# door_FM_rev_B.net
KiCad netlist of a schematic drawn in EAGLE
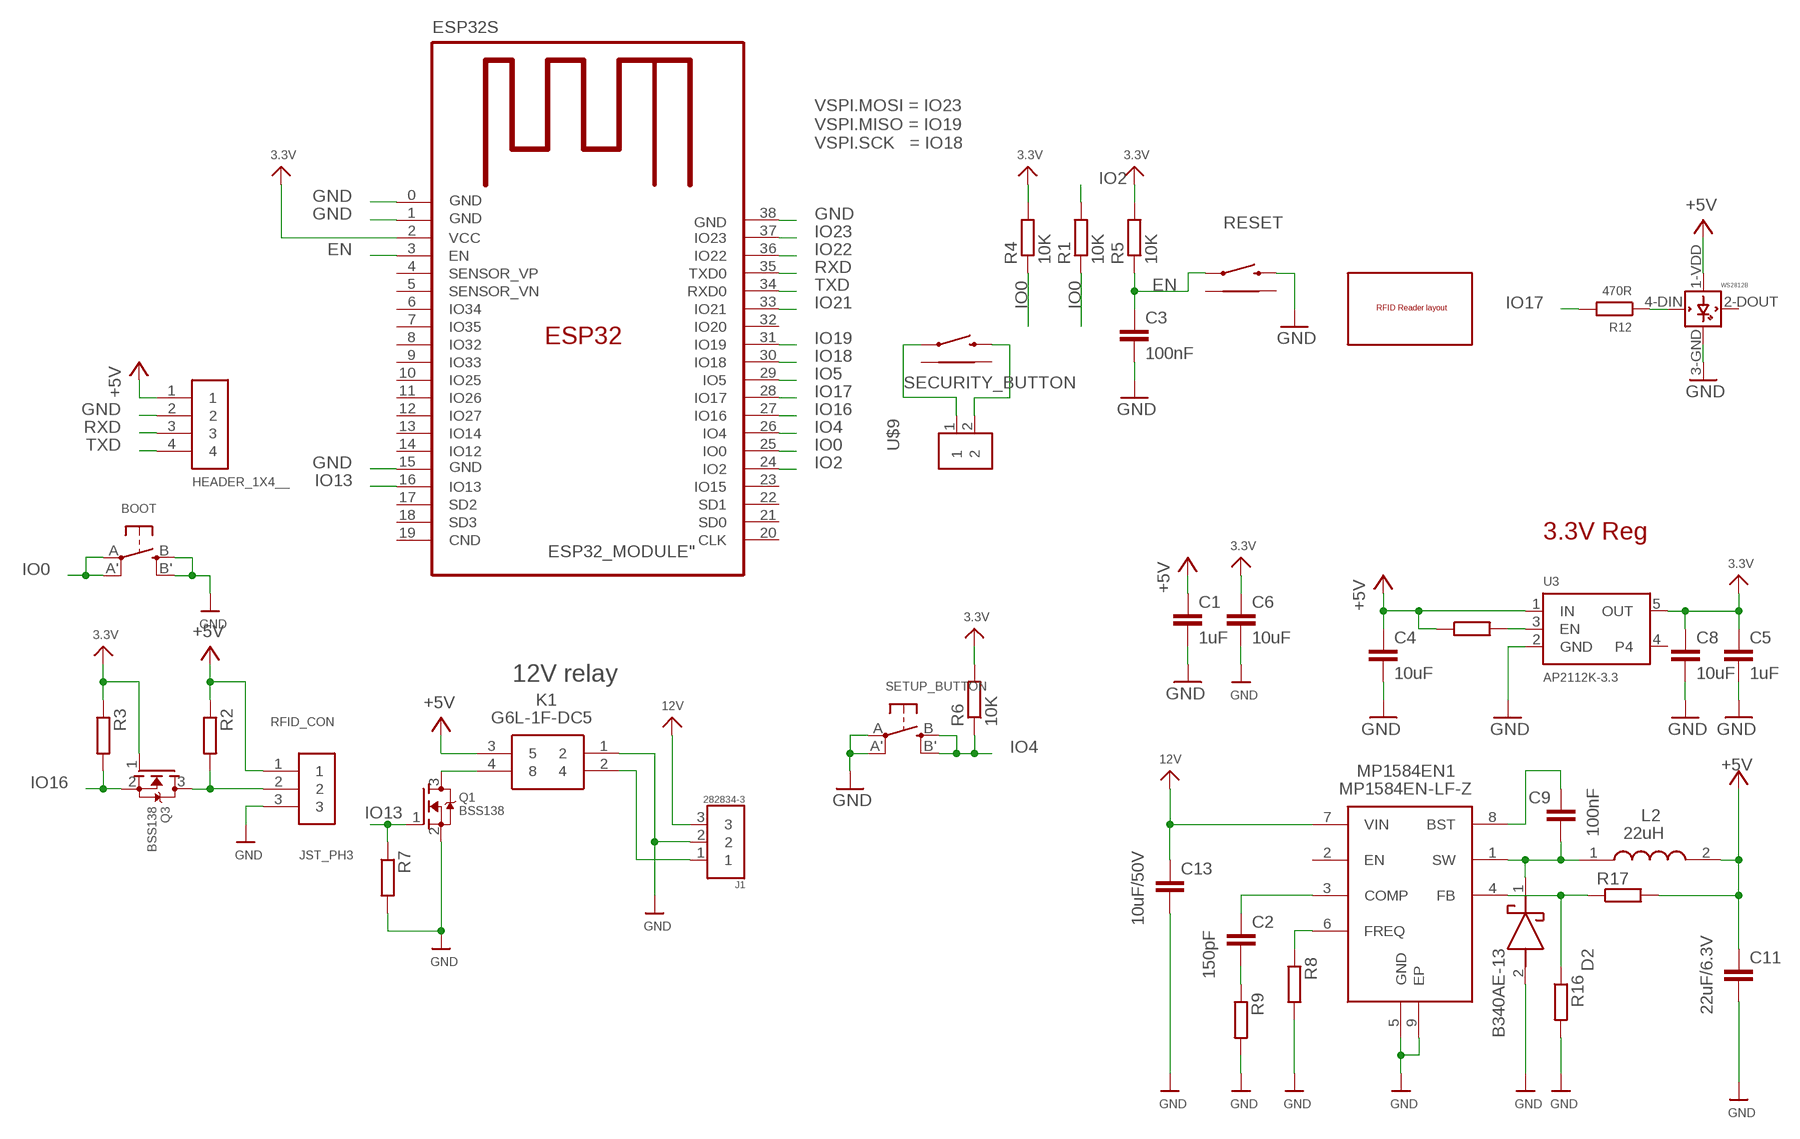
[diagram p0: schematic, sheet 1]

(export (version "E")
  (design (tool "Eeschema 10.0.6"))
  (components
    (comp (ref "BOOT")
      (value "BUTTON_KMR2_4.6X2.8")
      (footprint "eagle-import:BUTTON_KMR2_4.6X2.8")
      (libsource (lib "eagle-import") (part "BUTTON_KMR2_4.6X2.8"))
    )
    (comp (ref "C1")
      (value "1uF")
      (footprint "eagle-import:C0805")
      (libsource (lib "eagle-import") (part "C-EUC0805"))
    )
    (comp (ref "C2")
      (value "150pF")
      (footprint "eagle-import:C0805")
      (libsource (lib "eagle-import") (part "C-EUC0805"))
    )
    (comp (ref "C3")
      (value "100nF")
      (footprint "eagle-import:C0805")
      (libsource (lib "eagle-import") (part "C-EUC0805"))
    )
    (comp (ref "C4")
      (value "10uF")
      (footprint "eagle-import:C0805")
      (libsource (lib "eagle-import") (part "C-EUC0805"))
    )
    (comp (ref "C5")
      (value "1uF")
      (footprint "eagle-import:C0805")
      (libsource (lib "eagle-import") (part "C-EUC0805"))
    )
    (comp (ref "C6")
      (value "10uF")
      (footprint "eagle-import:C0805")
      (libsource (lib "eagle-import") (part "C-EUC0805"))
    )
    (comp (ref "C8")
      (value "10uF")
      (footprint "eagle-import:C0805")
      (libsource (lib "eagle-import") (part "C-EUC0805"))
    )
    (comp (ref "C9")
      (value "100nF")
      (footprint "eagle-import:C0805")
      (libsource (lib "eagle-import") (part "C-EUC0805"))
    )
    (comp (ref "C11")
      (value "22uF/6.3V")
      (footprint "eagle-import:C0805")
      (libsource (lib "eagle-import") (part "C-EUC0805"))
    )
    (comp (ref "C13")
      (value "10uF/50V")
      (footprint "eagle-import:C1206")
      (libsource (lib "eagle-import") (part "C-EUC1206"))
    )
    (comp (ref "CN1")
      (value "HEADER_1X4__")
      (footprint "eagle-import:HEADER_1X4_RIGHT_ANGLE")
      (libsource (lib "eagle-import") (part "HEADER_1X4__"))
    )
    (comp (ref "D2")
      (value "B340AE-13")
      (footprint "eagle-import:DIOM5226X240N")
      (fields (field (name "MOUSER_PART_NUMBER") "621-B340AE-13"))
      (libsource (lib "eagle-import") (part "B340AE-13"))
    )
    (comp (ref "ESP32S")
      (value "ESP32_MODULE\"")
      (footprint "eagle-import:ESP32_MODULE")
      (libsource (lib "eagle-import") (part "ESP32_MODULE{dblquote}"))
    )
    (comp (ref "J1")
      (value "282834-3")
      (footprint "eagle-import:TE_282834-3")
      (fields (field (name "MF") "TE Connectivity"))
      (libsource (lib "eagle-import") (part "282834-3"))
    )
    (comp (ref "K1")
      (value "G6L-1F-DC5")
      (footprint "eagle-import:G6L-1F-DC5")
      (fields (field (name "MOUSER_PART_NUMBER") "653-G6L-1F-DC5"))
      (libsource (lib "eagle-import") (part "G6L-1F-DC5"))
    )
    (comp (ref "L2")
      (value "22uH")
      (footprint "eagle-import:ASPI-0630LR")
      (fields
        (field (name "MANUFACTURER_PART_NUMBER") "ASPI-0630LR-4R7M-T15")
        (field (name "MOUSER_PART_NUMBER") "815-ASPI0630LR4R7T15")
      )
      (libsource (lib "eagle-import") (part "ASPI-0630LR-4R7M-T15"))
    )
    (comp (ref "MP1584EN1")
      (value "MP1584EN-LF-Z")
      (footprint "eagle-import:SOIC127P600X170-9N")
      (fields (field (name "MOUSER_PART_NUMBER") "946-MP1584ENLFZ"))
      (libsource (lib "eagle-import") (part "MP1584EN-LF-Z"))
    )
    (comp (ref "Q1")
      (value "BSS138")
      (footprint "eagle-import:SOT95P240X110-3")
      (libsource (lib "eagle-import") (part "MOSFET_N_"))
    )
    (comp (ref "Q3")
      (value "BSS138")
      (footprint "eagle-import:SOT95P240X110-3")
      (libsource (lib "eagle-import") (part "MOSFET_N_"))
    )
    (comp (ref "R1")
      (value "10K")
      (footprint "eagle-import:R0805")
      (libsource (lib "eagle-import") (part "R-EU_R0805"))
    )
    (comp (ref "R2")
      (value "10K")
      (footprint "eagle-import:R0805")
      (libsource (lib "eagle-import") (part "R-EU_R0805"))
    )
    (comp (ref "R3")
      (value "10K")
      (footprint "eagle-import:R0805")
      (libsource (lib "eagle-import") (part "R-EU_R0805"))
    )
    (comp (ref "R4")
      (value "10K")
      (footprint "eagle-import:R0805")
      (libsource (lib "eagle-import") (part "R-EU_R0805"))
    )
    (comp (ref "R5")
      (value "10K")
      (footprint "eagle-import:R0805")
      (libsource (lib "eagle-import") (part "R-EU_R0805"))
    )
    (comp (ref "R6")
      (value "10K")
      (footprint "eagle-import:R0805")
      (libsource (lib "eagle-import") (part "R-EU_R0805"))
    )
    (comp (ref "R7")
      (value "10K")
      (footprint "eagle-import:R0805")
      (libsource (lib "eagle-import") (part "R-EU_R0805"))
    )
    (comp (ref "R8")
      (value "100K")
      (footprint "eagle-import:R0805")
      (libsource (lib "eagle-import") (part "R-EU_R0805"))
    )
    (comp (ref "R9")
      (value "100K")
      (footprint "eagle-import:R0805")
      (libsource (lib "eagle-import") (part "R-EU_R0805"))
    )
    (comp (ref "R12")
      (value "470R")
      (footprint "eagle-import:R0805")
      (libsource (lib "eagle-import") (part "R-EU_R0805"))
    )
    (comp (ref "R16")
      (value "40K2")
      (footprint "eagle-import:R0805")
      (libsource (lib "eagle-import") (part "R-EU_R0805"))
    )
    (comp (ref "R17")
      (value "210K")
      (footprint "eagle-import:R0805")
      (libsource (lib "eagle-import") (part "R-EU_R0805"))
    )
    (comp (ref "R19")
      (value "10K")
      (footprint "eagle-import:R0805")
      (libsource (lib "eagle-import") (part "R-EU_R0805"))
    )
    (comp (ref "RESET")
      (value "TACTILE_SWITCH_RIGHT_ANGLE_THT_")
      (footprint "eagle-import:TACTILE_SWITCH_RIGHT_ANGLE_THT")
      (libsource (lib "eagle-import") (part "TACTILE_SWITCH_RIGHT_ANGLE_THT_"))
    )
    (comp (ref "RFID_CON")
      (value "JST_PH3")
      (footprint "eagle-import:JST-PH3")
      (libsource (lib "eagle-import") (part "JST_PH3"))
    )
    (comp (ref "SECURITY_BUTTON")
      (value "TACTILE_SWITCH_RIGHT_ANGLE_THT_")
      (footprint "eagle-import:TACTILE_SWITCH_RIGHT_ANGLE_THT")
      (libsource (lib "eagle-import") (part "TACTILE_SWITCH_RIGHT_ANGLE_THT_"))
    )
    (comp (ref "SETUP_BUTTON")
      (value "BUTTON_KMR2_4.6X2.8")
      (footprint "eagle-import:BUTTON_KMR2_4.6X2.8")
      (libsource (lib "eagle-import") (part "BUTTON_KMR2_4.6X2.8"))
    )
    (comp (ref "U$9")
      (value "282834-2")
      (footprint "eagle-import:CONN_282834-2")
      (fields (field (name "MF") "TE Connectivity"))
      (libsource (lib "eagle-import") (part "282834-2"))
    )
    (comp (ref "U$10")
      (value "RFID_READER")
      (footprint "eagle-import:RFID_READER")
      (libsource (lib "eagle-import") (part "RFID_READER"))
    )
    (comp (ref "U3")
      (value "AP2112K-3.3")
      (footprint "eagle-import:SOT95P290X120-5")
      (libsource (lib "eagle-import") (part "AP2112K-3.3_"))
    )
    (comp (ref "WS2812B")
      (value "WS2812B__")
      (footprint "eagle-import:WS2812B_5050")
      (libsource (lib "eagle-import") (part "WS2812B__"))
    )
  )
  (nets
    (net (code "1") (name "+5V") (class "Default")
      (node (ref "C1") (pin "1") (pinfunction "1_1") (pintype "passive"))
      (node (ref "C11") (pin "1") (pinfunction "1_1") (pintype "passive"))
      (node (ref "C4") (pin "1") (pinfunction "1_1") (pintype "passive"))
      (node (ref "CN1") (pin "1") (pinfunction "1_1") (pintype "bidirectional"))
      (node (ref "K1") (pin "3") (pinfunction "5_3") (pintype "bidirectional"))
      (node (ref "L2") (pin "2") (pinfunction "2_2") (pintype "bidirectional"))
      (node (ref "R17") (pin "2") (pinfunction "2_2") (pintype "passive"))
      (node (ref "R19") (pin "1") (pinfunction "1_1") (pintype "passive"))
      (node (ref "R2") (pin "1") (pinfunction "1_1") (pintype "passive"))
      (node (ref "RFID_CON") (pin "1") (pinfunction "1_1") (pintype "bidirectional"))
      (node (ref "U3") (pin "1") (pinfunction "IN_1") (pintype "bidirectional"))
      (node (ref "WS2812B") (pin "1-VDD") (pinfunction "VDD_1-VDD") (pintype "bidirectional"))
    )
    (net (code "2") (name "/EN") (class "Default")
      (node (ref "C3") (pin "1") (pinfunction "1_1") (pintype "passive"))
      (node (ref "ESP32S") (pin "3") (pinfunction "EN_3") (pintype "bidirectional"))
      (node (ref "R5") (pin "1") (pinfunction "1_1") (pintype "passive"))
      (node (ref "RESET") (pin "1") (pinfunction "1_1") (pintype "passive"))
    )
    (net (code "3") (name "/IO0") (class "Default")
      (node (ref "BOOT") (pin "A") (pinfunction "P_A") (pintype "passive"))
      (node (ref "BOOT") (pin "A'") (pinfunction "P1_A'") (pintype "passive"))
      (node (ref "ESP32S") (pin "25") (pinfunction "IO0_25") (pintype "bidirectional"))
      (node (ref "R1") (pin "1") (pinfunction "1_1") (pintype "passive"))
      (node (ref "R4") (pin "1") (pinfunction "1_1") (pintype "passive"))
    )
    (net (code "4") (name "/IO2") (class "Default")
      (node (ref "ESP32S") (pin "24") (pinfunction "IO2_24") (pintype "bidirectional"))
      (node (ref "R1") (pin "2") (pinfunction "2_2") (pintype "passive"))
    )
    (net (code "5") (name "/IO4") (class "Default")
      (node (ref "ESP32S") (pin "26") (pinfunction "IO4_26") (pintype "bidirectional"))
      (node (ref "R6") (pin "1") (pinfunction "1_1") (pintype "passive"))
      (node (ref "SETUP_BUTTON") (pin "B") (pinfunction "S_B") (pintype "passive"))
      (node (ref "SETUP_BUTTON") (pin "B'") (pinfunction "S1_B'") (pintype "passive"))
    )
    (net (code "6") (name "/IO5") (class "Default")
      (node (ref "ESP32S") (pin "29") (pinfunction "IO5_29") (pintype "bidirectional"))
    )
    (net (code "7") (name "/IO13") (class "Default")
      (node (ref "ESP32S") (pin "16") (pinfunction "IO13_16") (pintype "bidirectional"))
      (node (ref "Q1") (pin "1") (pinfunction "G_1") (pintype "bidirectional"))
      (node (ref "R7") (pin "1") (pinfunction "1_1") (pintype "passive"))
    )
    (net (code "8") (name "/IO16") (class "Default")
      (node (ref "ESP32S") (pin "27") (pinfunction "IO16_27") (pintype "bidirectional"))
      (node (ref "Q3") (pin "2") (pinfunction "S_2") (pintype "bidirectional"))
      (node (ref "R3") (pin "2") (pinfunction "2_2") (pintype "passive"))
    )
    (net (code "9") (name "/IO17") (class "Default")
      (node (ref "ESP32S") (pin "28") (pinfunction "IO17_28") (pintype "bidirectional"))
      (node (ref "R12") (pin "2") (pinfunction "2_2") (pintype "passive"))
    )
    (net (code "10") (name "/IO18") (class "Default")
      (node (ref "ESP32S") (pin "30") (pinfunction "IO18_30") (pintype "bidirectional"))
    )
    (net (code "11") (name "/IO19") (class "Default")
      (node (ref "ESP32S") (pin "31") (pinfunction "IO19_31") (pintype "bidirectional"))
    )
    (net (code "12") (name "/IO21") (class "Default")
      (node (ref "ESP32S") (pin "33") (pinfunction "IO21_33") (pintype "bidirectional"))
    )
    (net (code "13") (name "/IO22") (class "Default")
      (node (ref "ESP32S") (pin "36") (pinfunction "IO22_36") (pintype "bidirectional"))
    )
    (net (code "14") (name "/IO23") (class "Default")
      (node (ref "ESP32S") (pin "37") (pinfunction "IO23_37") (pintype "bidirectional"))
    )
    (net (code "15") (name "/RXD") (class "Default")
      (node (ref "CN1") (pin "3") (pinfunction "3_3") (pintype "bidirectional"))
      (node (ref "ESP32S") (pin "35") (pinfunction "TXD0_35") (pintype "bidirectional"))
    )
    (net (code "16") (name "/TXD") (class "Default")
      (node (ref "CN1") (pin "4") (pinfunction "4_4") (pintype "bidirectional"))
      (node (ref "ESP32S") (pin "34") (pinfunction "RXD0_34") (pintype "bidirectional"))
    )
    (net (code "17") (name "3.3V") (class "Default")
      (node (ref "C5") (pin "1") (pinfunction "1_1") (pintype "passive"))
      (node (ref "C6") (pin "1") (pinfunction "1_1") (pintype "passive"))
      (node (ref "C8") (pin "1") (pinfunction "1_1") (pintype "passive"))
      (node (ref "ESP32S") (pin "2") (pinfunction "VCC_2") (pintype "power_in"))
      (node (ref "Q3") (pin "1") (pinfunction "G_1") (pintype "bidirectional"))
      (node (ref "R3") (pin "1") (pinfunction "1_1") (pintype "passive"))
      (node (ref "R4") (pin "2") (pinfunction "2_2") (pintype "passive"))
      (node (ref "R5") (pin "2") (pinfunction "2_2") (pintype "passive"))
      (node (ref "R6") (pin "2") (pinfunction "2_2") (pintype "passive"))
      (node (ref "U3") (pin "5") (pinfunction "OUT_5") (pintype "bidirectional"))
    )
    (net (code "18") (name "12V") (class "Default")
      (node (ref "C13") (pin "1") (pinfunction "1_1") (pintype "passive"))
      (node (ref "J1") (pin "3") (pinfunction "3_3") (pintype "passive"))
      (node (ref "MP1584EN1") (pin "7") (pinfunction "VIN_7") (pintype "power_in"))
    )
    (net (code "19") (name "GND") (class "Default")
      (node (ref "BOOT") (pin "B") (pinfunction "S_B") (pintype "passive"))
      (node (ref "BOOT") (pin "B'") (pinfunction "S1_B'") (pintype "passive"))
      (node (ref "C1") (pin "2") (pinfunction "2_2") (pintype "passive"))
      (node (ref "C11") (pin "2") (pinfunction "2_2") (pintype "passive"))
      (node (ref "C13") (pin "2") (pinfunction "2_2") (pintype "passive"))
      (node (ref "C3") (pin "2") (pinfunction "2_2") (pintype "passive"))
      (node (ref "C4") (pin "2") (pinfunction "2_2") (pintype "passive"))
      (node (ref "C5") (pin "2") (pinfunction "2_2") (pintype "passive"))
      (node (ref "C6") (pin "2") (pinfunction "2_2") (pintype "passive"))
      (node (ref "C8") (pin "2") (pinfunction "2_2") (pintype "passive"))
      (node (ref "CN1") (pin "2") (pinfunction "2_2") (pintype "bidirectional"))
      (node (ref "D2") (pin "2") (pinfunction "A_2") (pintype "bidirectional"))
      (node (ref "ESP32S") (pin "0") (pinfunction "GND_0") (pintype "power_in"))
      (node (ref "ESP32S") (pin "1") (pinfunction "GND_1") (pintype "power_in"))
      (node (ref "ESP32S") (pin "15") (pinfunction "GND_15") (pintype "power_in"))
      (node (ref "ESP32S") (pin "38") (pinfunction "GND_38") (pintype "power_in"))
      (node (ref "J1") (pin "2") (pinfunction "2_2") (pintype "passive"))
      (node (ref "K1") (pin "1") (pinfunction "2_1") (pintype "bidirectional"))
      (node (ref "MP1584EN1") (pin "5") (pinfunction "GND_5") (pintype "power_in"))
      (node (ref "MP1584EN1") (pin "9") (pinfunction "EP_9") (pintype "bidirectional"))
      (node (ref "Q1") (pin "2") (pinfunction "S_2") (pintype "bidirectional"))
      (node (ref "R16") (pin "2") (pinfunction "2_2") (pintype "passive"))
      (node (ref "R7") (pin "2") (pinfunction "2_2") (pintype "passive"))
      (node (ref "R8") (pin "2") (pinfunction "2_2") (pintype "passive"))
      (node (ref "R9") (pin "2") (pinfunction "2_2") (pintype "passive"))
      (node (ref "RESET") (pin "2") (pinfunction "2_2") (pintype "passive"))
      (node (ref "RFID_CON") (pin "3") (pinfunction "3_3") (pintype "bidirectional"))
      (node (ref "SETUP_BUTTON") (pin "A") (pinfunction "P_A") (pintype "passive"))
      (node (ref "SETUP_BUTTON") (pin "A'") (pinfunction "P1_A'") (pintype "passive"))
      (node (ref "U3") (pin "2") (pinfunction "GND_2") (pintype "bidirectional"))
      (node (ref "WS2812B") (pin "3-GND") (pinfunction "GND_3-GND") (pintype "bidirectional"))
    )
    (net (code "20") (name "Net-(C2-Pad2)") (class "Default")
      (node (ref "C2") (pin "2") (pinfunction "2_2") (pintype "passive"))
      (node (ref "R9") (pin "1") (pinfunction "1_1") (pintype "passive"))
    )
    (net (code "21") (name "Net-(D2-K)") (class "Default")
      (node (ref "C9") (pin "2") (pinfunction "2_2") (pintype "passive"))
      (node (ref "D2") (pin "1") (pinfunction "K_1") (pintype "bidirectional"))
      (node (ref "L2") (pin "1") (pinfunction "1_1") (pintype "bidirectional"))
      (node (ref "MP1584EN1") (pin "1") (pinfunction "SW_1") (pintype "output"))
    )
    (net (code "22") (name "Net-(K1-4)") (class "Default")
      (node (ref "J1") (pin "1") (pinfunction "1_1") (pintype "passive"))
      (node (ref "K1") (pin "2") (pinfunction "4_2") (pintype "bidirectional"))
    )
    (net (code "23") (name "Net-(K1-8)") (class "Default")
      (node (ref "K1") (pin "4") (pinfunction "8_4") (pintype "bidirectional"))
      (node (ref "Q1") (pin "3") (pinfunction "D_3") (pintype "bidirectional"))
    )
    (net (code "24") (name "Net-(MP1584EN1-BST)") (class "Default")
      (node (ref "C9") (pin "1") (pinfunction "1_1") (pintype "passive"))
      (node (ref "MP1584EN1") (pin "8") (pinfunction "BST_8") (pintype "input"))
    )
    (net (code "25") (name "Net-(MP1584EN1-COMP)") (class "Default")
      (node (ref "C2") (pin "1") (pinfunction "1_1") (pintype "passive"))
      (node (ref "MP1584EN1") (pin "3") (pinfunction "COMP_3") (pintype "bidirectional"))
    )
    (net (code "26") (name "Net-(MP1584EN1-FB)") (class "Default")
      (node (ref "MP1584EN1") (pin "4") (pinfunction "FB_4") (pintype "input"))
      (node (ref "R16") (pin "1") (pinfunction "1_1") (pintype "passive"))
      (node (ref "R17") (pin "1") (pinfunction "1_1") (pintype "passive"))
    )
    (net (code "27") (name "Net-(MP1584EN1-FREQ)") (class "Default")
      (node (ref "MP1584EN1") (pin "6") (pinfunction "FREQ_6") (pintype "input"))
      (node (ref "R8") (pin "1") (pinfunction "1_1") (pintype "passive"))
    )
    (net (code "28") (name "Net-(Q3-D)") (class "Default")
      (node (ref "Q3") (pin "3") (pinfunction "D_3") (pintype "bidirectional"))
      (node (ref "R2") (pin "2") (pinfunction "2_2") (pintype "passive"))
      (node (ref "RFID_CON") (pin "2") (pinfunction "2_2") (pintype "bidirectional"))
    )
    (net (code "29") (name "Net-(SECURITY_BUTTON-Pad1)") (class "Default")
      (node (ref "SECURITY_BUTTON") (pin "1") (pinfunction "1_1") (pintype "passive"))
      (node (ref "U$9") (pin "1") (pinfunction "1_1") (pintype "passive"))
    )
    (net (code "30") (name "Net-(SECURITY_BUTTON-Pad2)") (class "Default")
      (node (ref "SECURITY_BUTTON") (pin "2") (pinfunction "2_2") (pintype "passive"))
      (node (ref "U$9") (pin "2") (pinfunction "2_2") (pintype "passive"))
    )
    (net (code "31") (name "Net-(U3-EN)") (class "Default")
      (node (ref "R19") (pin "2") (pinfunction "2_2") (pintype "passive"))
      (node (ref "U3") (pin "3") (pinfunction "EN_3") (pintype "bidirectional"))
    )
    (net (code "32") (name "Net-(WS2812B-DIN)") (class "Default")
      (node (ref "R12") (pin "1") (pinfunction "1_1") (pintype "passive"))
      (node (ref "WS2812B") (pin "4-DIN") (pinfunction "DIN_4-DIN") (pintype "input"))
    )
    (net (code "33") (name "unconnected-(ESP32S-CLK-Pad20)") (class "Default")
      (node (ref "ESP32S") (pin "20") (pinfunction "CLK_20") (pintype "bidirectional"))
    )
    (net (code "34") (name "unconnected-(ESP32S-CND-Pad19)") (class "Default")
      (node (ref "ESP32S") (pin "19") (pinfunction "CND_19") (pintype "bidirectional"))
    )
    (net (code "35") (name "unconnected-(ESP32S-IO12-Pad14)") (class "Default")
      (node (ref "ESP32S") (pin "14") (pinfunction "IO12_14") (pintype "bidirectional"))
    )
    (net (code "36") (name "unconnected-(ESP32S-IO14-Pad13)") (class "Default")
      (node (ref "ESP32S") (pin "13") (pinfunction "IO14_13") (pintype "bidirectional"))
    )
    (net (code "37") (name "unconnected-(ESP32S-IO15-Pad23)") (class "Default")
      (node (ref "ESP32S") (pin "23") (pinfunction "IO15_23") (pintype "bidirectional"))
    )
    (net (code "38") (name "unconnected-(ESP32S-IO20-Pad32)") (class "Default")
      (node (ref "ESP32S") (pin "32") (pinfunction "IO20_32") (pintype "bidirectional"))
    )
    (net (code "39") (name "unconnected-(ESP32S-IO25-Pad10)") (class "Default")
      (node (ref "ESP32S") (pin "10") (pinfunction "IO25_10") (pintype "bidirectional"))
    )
    (net (code "40") (name "unconnected-(ESP32S-IO26-Pad11)") (class "Default")
      (node (ref "ESP32S") (pin "11") (pinfunction "IO26_11") (pintype "bidirectional"))
    )
    (net (code "41") (name "unconnected-(ESP32S-IO27-Pad12)") (class "Default")
      (node (ref "ESP32S") (pin "12") (pinfunction "IO27_12") (pintype "bidirectional"))
    )
    (net (code "42") (name "unconnected-(ESP32S-IO32-Pad8)") (class "Default")
      (node (ref "ESP32S") (pin "8") (pinfunction "IO32_8") (pintype "bidirectional"))
    )
    (net (code "43") (name "unconnected-(ESP32S-IO33-Pad9)") (class "Default")
      (node (ref "ESP32S") (pin "9") (pinfunction "IO33_9") (pintype "bidirectional"))
    )
    (net (code "44") (name "unconnected-(ESP32S-IO34-Pad6)") (class "Default")
      (node (ref "ESP32S") (pin "6") (pinfunction "IO34_6") (pintype "bidirectional"))
    )
    (net (code "45") (name "unconnected-(ESP32S-IO35-Pad7)") (class "Default")
      (node (ref "ESP32S") (pin "7") (pinfunction "IO35_7") (pintype "bidirectional"))
    )
    (net (code "46") (name "unconnected-(ESP32S-SD0-Pad21)") (class "Default")
      (node (ref "ESP32S") (pin "21") (pinfunction "SD0_21") (pintype "bidirectional"))
    )
    (net (code "47") (name "unconnected-(ESP32S-SD1-Pad22)") (class "Default")
      (node (ref "ESP32S") (pin "22") (pinfunction "SD1_22") (pintype "bidirectional"))
    )
    (net (code "48") (name "unconnected-(ESP32S-SD2-Pad17)") (class "Default")
      (node (ref "ESP32S") (pin "17") (pinfunction "SD2_17") (pintype "bidirectional"))
    )
    (net (code "49") (name "unconnected-(ESP32S-SD3-Pad18)") (class "Default")
      (node (ref "ESP32S") (pin "18") (pinfunction "SD3_18") (pintype "bidirectional"))
    )
    (net (code "50") (name "unconnected-(ESP32S-SENSOR_VN-Pad5)") (class "Default")
      (node (ref "ESP32S") (pin "5") (pinfunction "SENSOR_VN_5") (pintype "bidirectional"))
    )
    (net (code "51") (name "unconnected-(ESP32S-SENSOR_VP-Pad4)") (class "Default")
      (node (ref "ESP32S") (pin "4") (pinfunction "SENSOR_VP_4") (pintype "bidirectional"))
    )
    (net (code "52") (name "unconnected-(MP1584EN1-EN-Pad2)") (class "Default")
      (node (ref "MP1584EN1") (pin "2") (pinfunction "EN_2") (pintype "input"))
    )
    (net (code "53") (name "unconnected-(RESET-3-PadANCHOR1)") (class "Default")
      (node (ref "RESET") (pin "ANCHOR1") (pinfunction "3_ANCHOR1") (pintype "passive"))
    )
    (net (code "54") (name "unconnected-(RESET-4-PadANCHOR2)") (class "Default")
      (node (ref "RESET") (pin "ANCHOR2") (pinfunction "4_ANCHOR2") (pintype "passive"))
    )
    (net (code "55") (name "unconnected-(SECURITY_BUTTON-3-PadANCHOR1)") (class "Default")
      (node (ref "SECURITY_BUTTON") (pin "ANCHOR1") (pinfunction "3_ANCHOR1") (pintype "passive"))
    )
    (net (code "56") (name "unconnected-(SECURITY_BUTTON-4-PadANCHOR2)") (class "Default")
      (node (ref "SECURITY_BUTTON") (pin "ANCHOR2") (pinfunction "4_ANCHOR2") (pintype "passive"))
    )
    (net (code "57") (name "unconnected-(U3-P4-Pad4)") (class "Default")
      (node (ref "U3") (pin "4") (pinfunction "P4_4") (pintype "bidirectional"))
    )
    (net (code "58") (name "unconnected-(WS2812B-DOUT-Pad2-DOUT)") (class "Default")
      (node (ref "WS2812B") (pin "2-DOUT") (pinfunction "DOUT_2-DOUT") (pintype "output"))
    )
  )
)
